# TPS63901_BuckBoost_lowIq_3V3_2V3_400mA.net
KiCad netlist of a schematic drawn in Altium Designer
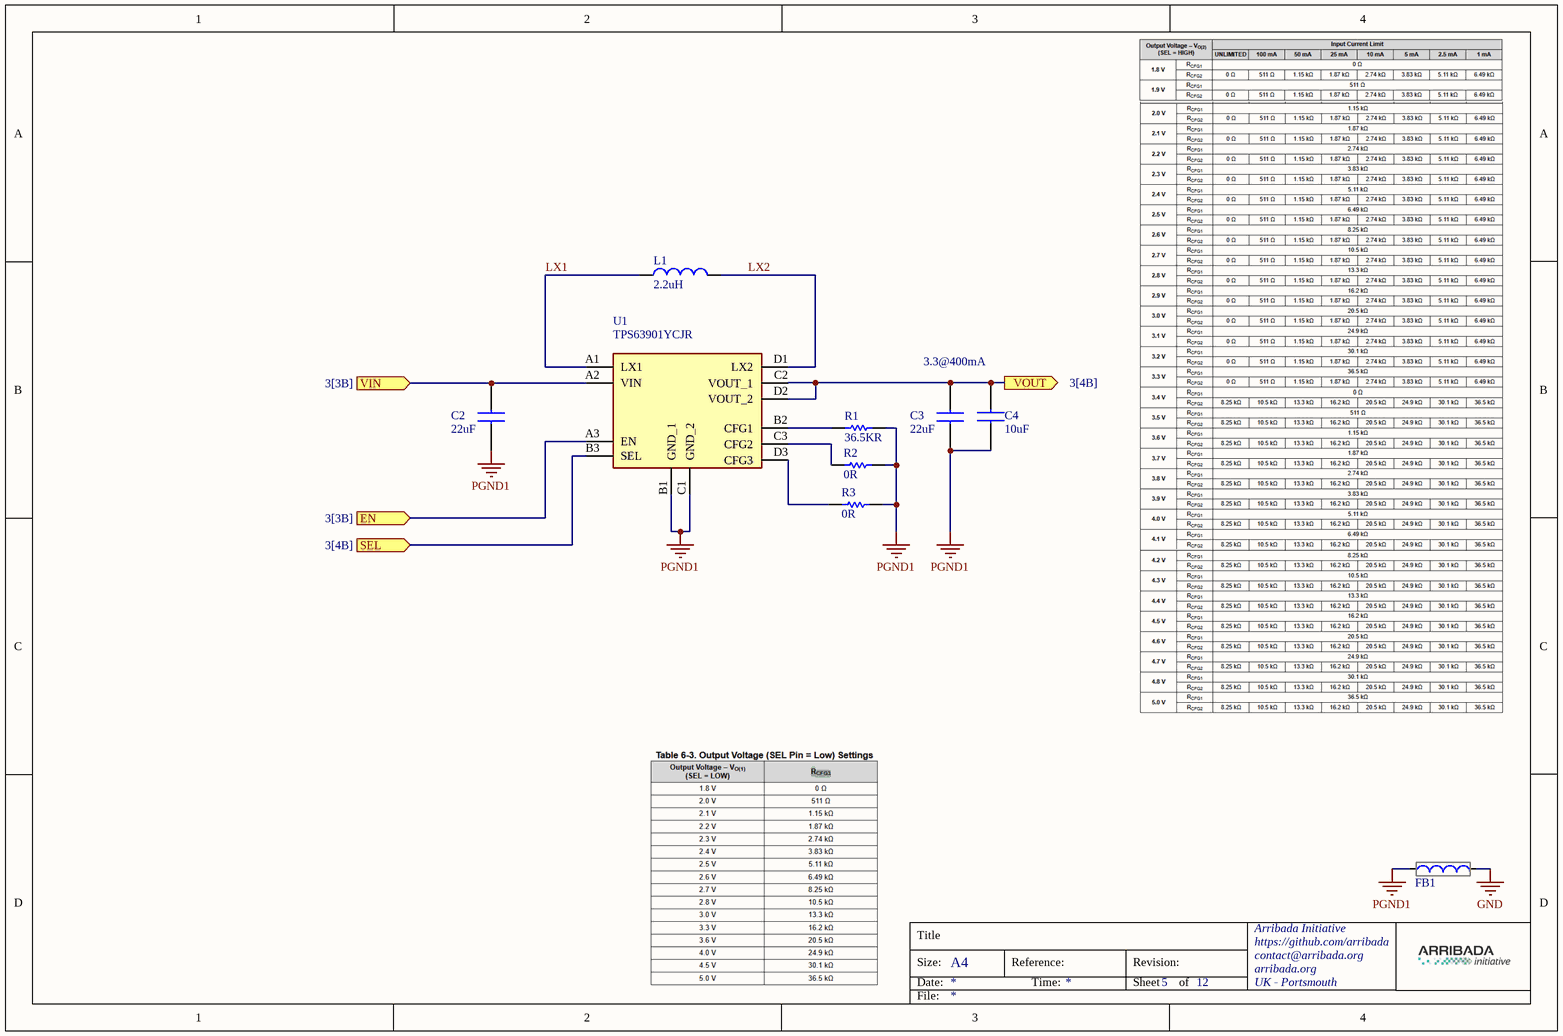
[diagram p0: TPS63901_BuckBoost_lowIq_3V3&2V3_400mA.SchDoc]

(export (version "E")
  (design (tool "Eeschema 10.0.6"))
  (components
    (comp (ref "C2")
      (value "22uF")
      (footprint "GRM18x")
      (description "Multilayer Ceramic Capacitors MLCC - SMD/SMT 22 uF 10 VDC 20% 0603 X5R")
      (fields
        (field (name "MANUFACTURER_PART_NUMBER") "GRM188R61A226ME15D")
        (field (name "MOUSER PART NUMBER") "81-GRM188R61A226ME5D")
      )
      (libsource (lib "stm32wl-dev") (part "GRM188R61A226ME15D"))
    )
    (comp (ref "C3")
      (value "22uF")
      (footprint "GRM18x")
      (description "Multilayer Ceramic Capacitors MLCC - SMD/SMT 22 uF 10 VDC 20% 0603 X5R")
      (fields
        (field (name "MANUFACTURER_PART_NUMBER") "GRM188R61A226ME15D")
        (field (name "MOUSER PART NUMBER") "81-GRM188R61A226ME5D")
      )
      (libsource (lib "stm32wl-dev") (part "GRM188R61A226ME15D"))
    )
    (comp (ref "C4")
      (value "10uF")
      (footprint "CAPC1608X90N")
      (description "Multilayer Ceramic Capacitors MLCC - SMD/SMT 10 uF 10 VDC 20% 0603 X5R")
      (fields
        (field (name "MANUFACTURER_PART_NUMBER") "GRM188R61A106MAALJ")
        (field (name "MOUSER PART NUMBER") "81-GRM188R61A106MALJ")
      )
      (libsource (lib "stm32wl-dev") (part "GRM188R61A106MAALJ"))
    )
    (comp (ref "FB1")
      (value "BLM18AG102SN1D")
      (footprint "stm32wl-dev:BLM18SP221SN1B")
      (description "Ferrite Bead - 1000 OHM 25%")
      (fields (field (name "MOUSER PART NUMBER") "81-BLM11A102S"))
      (libsource (lib "stm32wl-dev") (part "BLM18AG102SN1D"))
    )
    (comp (ref "L1")
      (value "2.2uH")
      (footprint "DFE2HCAH1R0MJ0L")
      (description "Inductor Power Chip Shielded Wirewound 2.2uH 20% 1MHz Metal 2.3A 0.082Ohm DCR 1008 T/R")
      (fields
        (field (name "MANUFACTURER") "Murata")
        (field (name "MANUFACTURER PART NUMBER") "DFE252012F-2R2M=P2")
      )
      (libsource (lib "stm32wl-dev") (part "DFE252012F-2R2M=P2"))
    )
    (comp (ref "R1")
      (value "36.5KR")
      (footprint "RESC0603X28N")
      (description "Thick Film Resistors - SMD 36.5Kohm 1% 200ppm")
      (fields (field (name "MANUFACTURER_PART_NUMBER") "CRCW020136K5FNED"))
      (libsource (lib "stm32wl-dev") (part "CRCW020136K5FNED"))
    )
    (comp (ref "R2")
      (value "0R")
      (footprint "RESC0603X26N")
      (description "Thick Film Resistors - SMD 0 Ohms 50mW 0201 1%")
      (fields
        (field (name "MANUFACTURER_PART_NUMBER") "RC0201FR-070RL")
        (field (name "MOUSER PART NUMBER") "603-RC0201FR-070RL")
      )
      (libsource (lib "stm32wl-dev") (part "RC0201FR-070RL"))
    )
    (comp (ref "R3")
      (value "0R")
      (footprint "RESC0603X26N")
      (description "Thick Film Resistors - SMD 0 Ohms 50mW 0201 1%")
      (fields
        (field (name "MANUFACTURER_PART_NUMBER") "RC0201FR-070RL")
        (field (name "MOUSER PART NUMBER") "603-RC0201FR-070RL")
      )
      (libsource (lib "stm32wl-dev") (part "RC0201FR-070RL"))
    )
    (comp (ref "U1")
      (value "TPS63901YCJR")
      (footprint "BGA12C35P3X4_111X146X35")
      (description "Switching Voltage Regulators 5.5-V buck-boost con verter with 75-nA op")
      (fields (field (name "MOUSER PART NUMBER") "595-TPS63901YCJR"))
      (libsource (lib "stm32wl-dev") (part "TPS63901YCJR"))
    )
  )
  (nets
    (net (code "1") (name "/EN") (class "Default")
      (node (ref "U1") (pin "A3") (pinfunction "EN_A3") (pintype "passive"))
    )
    (net (code "2") (name "/LX1") (class "Default")
      (node (ref "L1") (pin "1") (pinfunction "1_1") (pintype "passive"))
      (node (ref "U1") (pin "A1") (pinfunction "LX1_A1") (pintype "passive"))
    )
    (net (code "3") (name "/LX2") (class "Default")
      (node (ref "L1") (pin "2") (pinfunction "2_2") (pintype "passive"))
      (node (ref "U1") (pin "D1") (pinfunction "LX2_D1") (pintype "passive"))
    )
    (net (code "4") (name "/SEL") (class "Default")
      (node (ref "U1") (pin "B3") (pinfunction "SEL_B3") (pintype "passive"))
    )
    (net (code "5") (name "/VIN") (class "Default")
      (node (ref "C2") (pin "1") (pinfunction "1_1") (pintype "passive"))
      (node (ref "U1") (pin "A2") (pinfunction "VIN_A2") (pintype "passive"))
    )
    (net (code "6") (name "/VOUT") (class "Default")
      (node (ref "C3") (pin "1") (pinfunction "1_1") (pintype "passive"))
      (node (ref "C4") (pin "1") (pinfunction "1_1") (pintype "passive"))
      (node (ref "U1") (pin "C2") (pinfunction "VOUT_1_C2") (pintype "passive"))
      (node (ref "U1") (pin "D2") (pinfunction "VOUT_2_D2") (pintype "passive"))
    )
    (net (code "7") (name "GND") (class "Default")
      (node (ref "FB1") (pin "2") (pinfunction "2_2") (pintype "passive"))
    )
    (net (code "8") (name "Net-(U1-CFG1)") (class "Default")
      (node (ref "R1") (pin "1") (pinfunction "1_1") (pintype "passive"))
      (node (ref "U1") (pin "B2") (pinfunction "CFG1_B2") (pintype "passive"))
    )
    (net (code "9") (name "Net-(U1-CFG2)") (class "Default")
      (node (ref "R2") (pin "1") (pinfunction "1_1") (pintype "passive"))
      (node (ref "U1") (pin "C3") (pinfunction "CFG2_C3") (pintype "passive"))
    )
    (net (code "10") (name "Net-(U1-CFG3)") (class "Default")
      (node (ref "R3") (pin "2") (pinfunction "2_2") (pintype "passive"))
      (node (ref "U1") (pin "D3") (pinfunction "CFG3_D3") (pintype "passive"))
    )
    (net (code "11") (name "PGND1") (class "Default")
      (node (ref "C2") (pin "2") (pinfunction "2_2") (pintype "passive"))
      (node (ref "C3") (pin "2") (pinfunction "2_2") (pintype "passive"))
      (node (ref "C4") (pin "2") (pinfunction "2_2") (pintype "passive"))
      (node (ref "FB1") (pin "1") (pinfunction "1_1") (pintype "passive"))
      (node (ref "R1") (pin "2") (pinfunction "2_2") (pintype "passive"))
      (node (ref "R2") (pin "2") (pinfunction "2_2") (pintype "passive"))
      (node (ref "R3") (pin "1") (pinfunction "1_1") (pintype "passive"))
      (node (ref "U1") (pin "B1") (pinfunction "GND_1_B1") (pintype "passive"))
      (node (ref "U1") (pin "C1") (pinfunction "GND_2_C1") (pintype "passive"))
    )
  )
)
